# arduino_semaphore.net
KiCad netlist of a schematic drawn in EAGLE
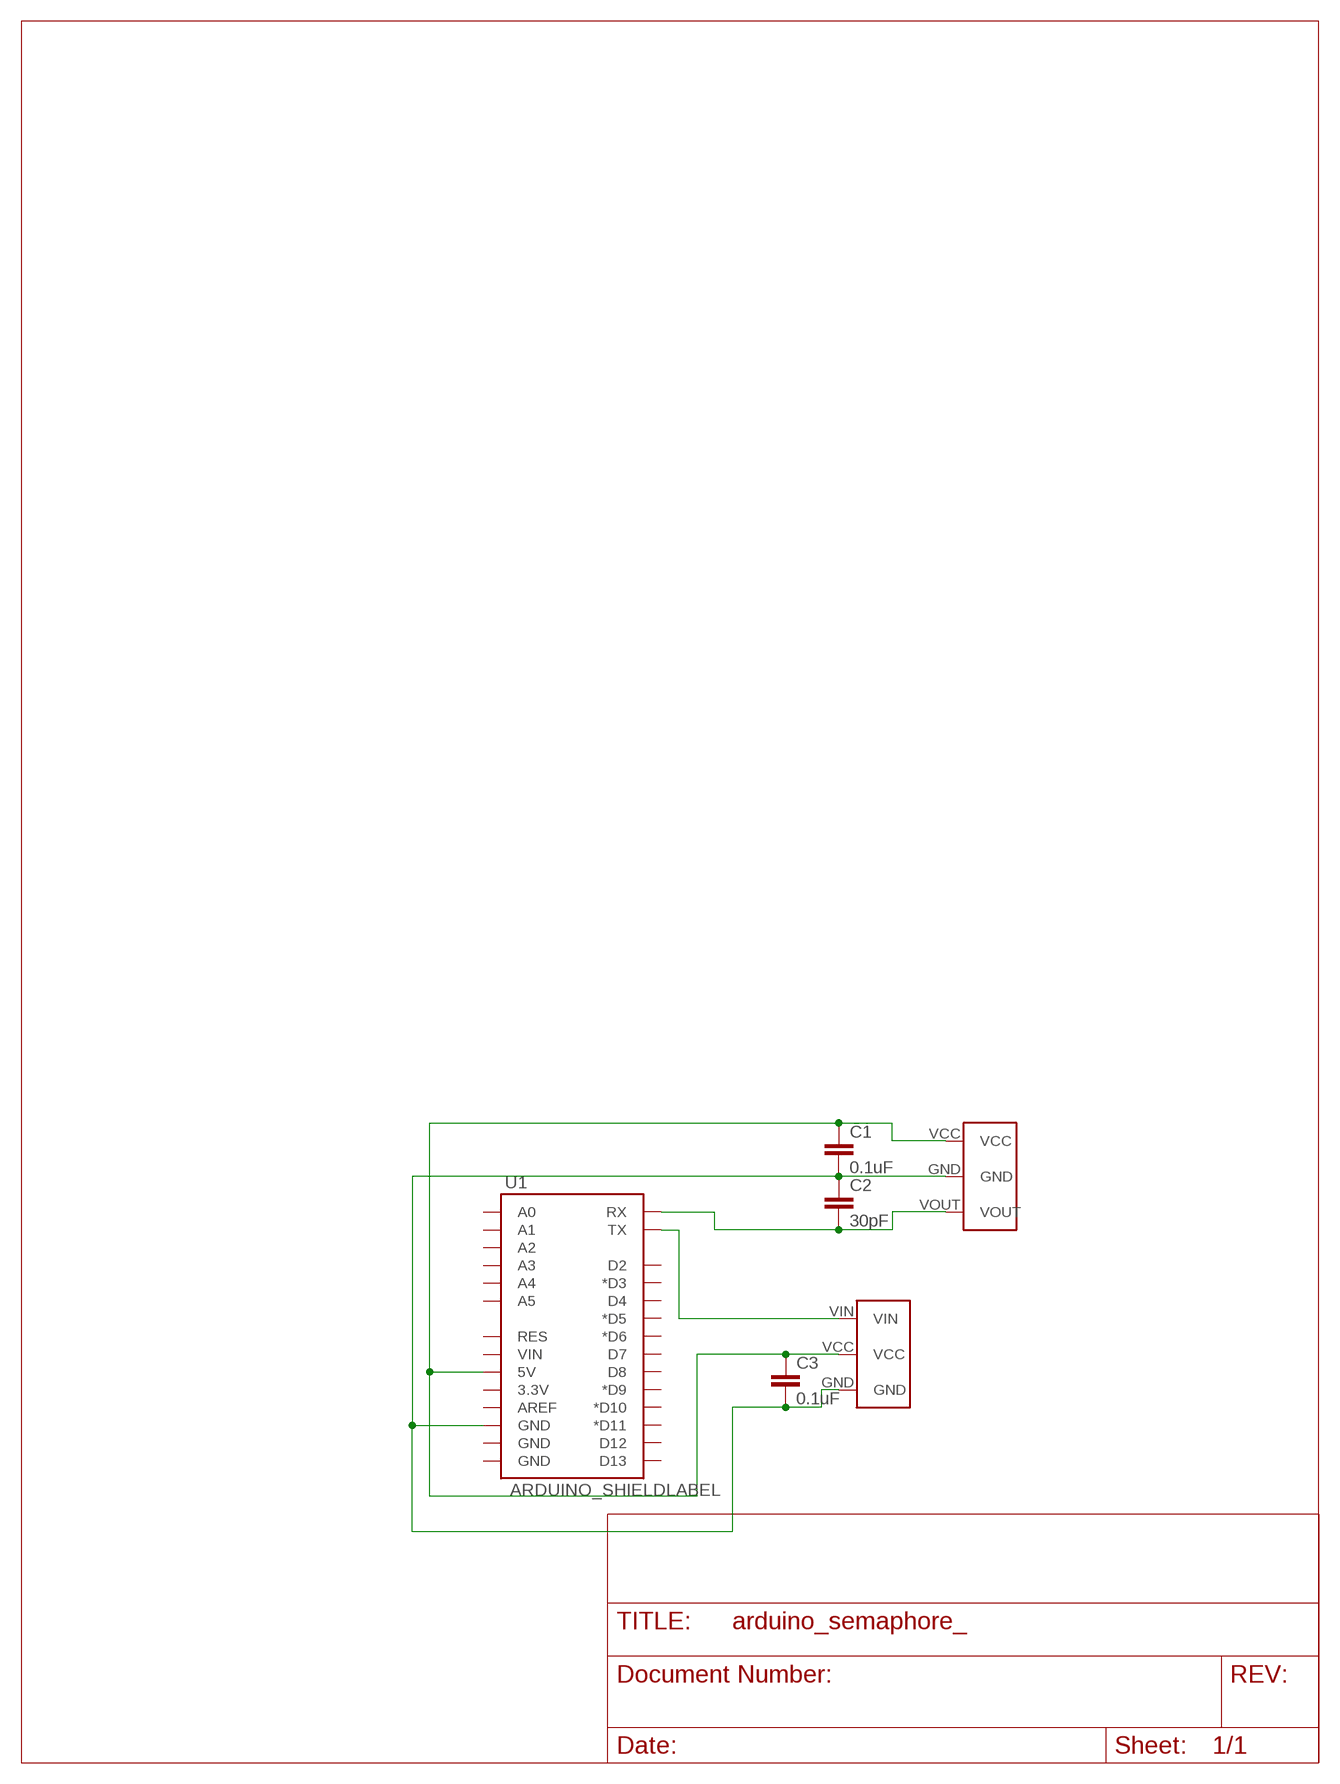
[diagram p0: schematic, sheet 1]

(export (version "E")
  (design (tool "Eeschema 10.0.6"))
  (components
    (comp (ref "C1")
      (value "0.1uF")
      (footprint "eagle-import:0805")
      (libsource (lib "eagle-import") (part "CAP0805"))
    )
    (comp (ref "C2")
      (value "30pF")
      (footprint "eagle-import:0805")
      (libsource (lib "eagle-import") (part "CAP0805"))
    )
    (comp (ref "C3")
      (value "0.1uF")
      (footprint "eagle-import:0805")
      (libsource (lib "eagle-import") (part "CAP0805"))
    )
    (comp (ref "U$1")
      (value "DLR1160")
      (footprint "eagle-import:DLR")
      (libsource (lib "eagle-import") (part "DLR1160"))
    )
    (comp (ref "U$2")
      (value "DLT1160")
      (footprint "eagle-import:DLT")
      (libsource (lib "eagle-import") (part "DLT1160"))
    )
    (comp (ref "U1")
      (value "ARDUINO_SHIELDLABEL")
      (footprint "eagle-import:DUEMILANOVE_SHIELD")
      (libsource (lib "eagle-import") (part "ARDUINO_SHIELDLABEL"))
    )
  )
  (nets
    (net (code "1") (name "Net-(C1-Pad1)") (class "Default")
      (node (ref "C1") (pin "1") (pinfunction "1_1") (pintype "passive"))
      (node (ref "C3") (pin "1") (pinfunction "1_1") (pintype "passive"))
      (node (ref "U$1") (pin "VCC") (pinfunction "VCC_VCC") (pintype "bidirectional"))
      (node (ref "U$2") (pin "VCC") (pinfunction "VCC_VCC") (pintype "bidirectional"))
      (node (ref "U1") (pin "5V") (pinfunction "5V_5V") (pintype "bidirectional"))
    )
    (net (code "2") (name "Net-(C1-Pad2)") (class "Default")
      (node (ref "C1") (pin "2") (pinfunction "2_2") (pintype "passive"))
      (node (ref "C2") (pin "1") (pinfunction "1_1") (pintype "passive"))
      (node (ref "C3") (pin "2") (pinfunction "2_2") (pintype "passive"))
      (node (ref "U$1") (pin "GND") (pinfunction "GND_GND") (pintype "bidirectional"))
      (node (ref "U$2") (pin "GND") (pinfunction "GND_GND") (pintype "bidirectional"))
      (node (ref "U1") (pin "GND@2") (pinfunction "GND_GND@2") (pintype "bidirectional"))
    )
    (net (code "3") (name "Net-(C2-Pad2)") (class "Default")
      (node (ref "C2") (pin "2") (pinfunction "2_2") (pintype "passive"))
      (node (ref "U$1") (pin "VOUT") (pinfunction "VOUT_VOUT") (pintype "bidirectional"))
      (node (ref "U1") (pin "RX") (pinfunction "RX_RX") (pintype "bidirectional"))
    )
    (net (code "4") (name "Net-(U$2-PadVIN)") (class "Default")
      (node (ref "U$2") (pin "VIN") (pinfunction "VIN_VIN") (pintype "bidirectional"))
      (node (ref "U1") (pin "TX") (pinfunction "TX_TX") (pintype "bidirectional"))
    )
    (net (code "5") (name "unconnected-(U1-*D3-PadD3)") (class "Default")
      (node (ref "U1") (pin "D3") (pinfunction "*D3_D3") (pintype "bidirectional"))
    )
    (net (code "6") (name "unconnected-(U1-*D5-PadD5)") (class "Default")
      (node (ref "U1") (pin "D5") (pinfunction "*D5_D5") (pintype "bidirectional"))
    )
    (net (code "7") (name "unconnected-(U1-*D6-PadD6)") (class "Default")
      (node (ref "U1") (pin "D6") (pinfunction "*D6_D6") (pintype "bidirectional"))
    )
    (net (code "8") (name "unconnected-(U1-*D9-PadD9)") (class "Default")
      (node (ref "U1") (pin "D9") (pinfunction "*D9_D9") (pintype "bidirectional"))
    )
    (net (code "9") (name "unconnected-(U1-*D10-PadD10)") (class "Default")
      (node (ref "U1") (pin "D10") (pinfunction "*D10_D10") (pintype "bidirectional"))
    )
    (net (code "10") (name "unconnected-(U1-*D11-PadD11)") (class "Default")
      (node (ref "U1") (pin "D11") (pinfunction "*D11_D11") (pintype "bidirectional"))
    )
    (net (code "11") (name "unconnected-(U1-GND-PadGND@0)") (class "Default")
      (node (ref "U1") (pin "GND@0") (pinfunction "GND_GND@0") (pintype "bidirectional"))
    )
    (net (code "12") (name "unconnected-(U1-GND-PadGND@1)") (class "Default")
      (node (ref "U1") (pin "GND@1") (pinfunction "GND_GND@1") (pintype "bidirectional"))
    )
    (net (code "13") (name "unconnected-(U1-Pad3.3V)") (class "Default")
      (node (ref "U1") (pin "3.3V") (pinfunction "3.3V_3.3V") (pintype "bidirectional"))
    )
    (net (code "14") (name "unconnected-(U1-PadA0)") (class "Default")
      (node (ref "U1") (pin "A0") (pinfunction "A0_A0") (pintype "bidirectional"))
    )
    (net (code "15") (name "unconnected-(U1-PadA1)") (class "Default")
      (node (ref "U1") (pin "A1") (pinfunction "A1_A1") (pintype "bidirectional"))
    )
    (net (code "16") (name "unconnected-(U1-PadA2)") (class "Default")
      (node (ref "U1") (pin "A2") (pinfunction "A2_A2") (pintype "bidirectional"))
    )
    (net (code "17") (name "unconnected-(U1-PadA3)") (class "Default")
      (node (ref "U1") (pin "A3") (pinfunction "A3_A3") (pintype "bidirectional"))
    )
    (net (code "18") (name "unconnected-(U1-PadA4)") (class "Default")
      (node (ref "U1") (pin "A4") (pinfunction "A4_A4") (pintype "bidirectional"))
    )
    (net (code "19") (name "unconnected-(U1-PadA5)") (class "Default")
      (node (ref "U1") (pin "A5") (pinfunction "A5_A5") (pintype "bidirectional"))
    )
    (net (code "20") (name "unconnected-(U1-PadAREF)") (class "Default")
      (node (ref "U1") (pin "AREF") (pinfunction "AREF_AREF") (pintype "bidirectional"))
    )
    (net (code "21") (name "unconnected-(U1-PadD2)") (class "Default")
      (node (ref "U1") (pin "D2") (pinfunction "D2_D2") (pintype "bidirectional"))
    )
    (net (code "22") (name "unconnected-(U1-PadD4)") (class "Default")
      (node (ref "U1") (pin "D4") (pinfunction "D4_D4") (pintype "bidirectional"))
    )
    (net (code "23") (name "unconnected-(U1-PadD7)") (class "Default")
      (node (ref "U1") (pin "D7") (pinfunction "D7_D7") (pintype "bidirectional"))
    )
    (net (code "24") (name "unconnected-(U1-PadD8)") (class "Default")
      (node (ref "U1") (pin "D8") (pinfunction "D8_D8") (pintype "bidirectional"))
    )
    (net (code "25") (name "unconnected-(U1-PadD12)") (class "Default")
      (node (ref "U1") (pin "D12") (pinfunction "D12_D12") (pintype "bidirectional"))
    )
    (net (code "26") (name "unconnected-(U1-PadD13)") (class "Default")
      (node (ref "U1") (pin "D13") (pinfunction "D13_D13") (pintype "bidirectional"))
    )
    (net (code "27") (name "unconnected-(U1-PadRES)") (class "Default")
      (node (ref "U1") (pin "RES") (pinfunction "RES_RES") (pintype "bidirectional"))
    )
    (net (code "28") (name "unconnected-(U1-PadVIN)") (class "Default")
      (node (ref "U1") (pin "VIN") (pinfunction "VIN_VIN") (pintype "bidirectional"))
    )
  )
)
